# analog.net
KiCad netlist of a schematic drawn in Altium Designer
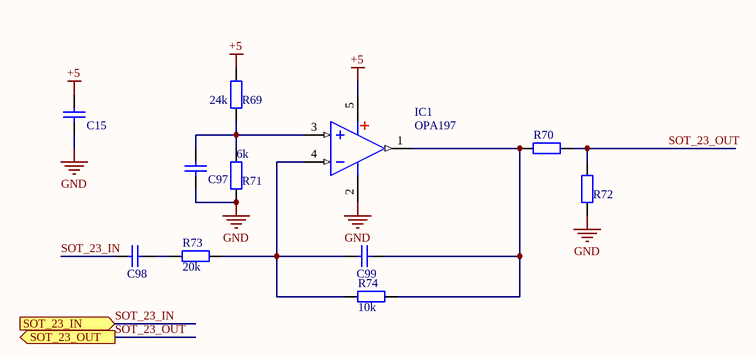
[diagram p0: analog.SchDoc]

(export (version "E")
  (design (tool "Eeschema 10.0.6"))
  (components
    (comp (ref "C15")
      (value "10nF (103) 10% 50V")
      (footprint "0603_C")
      (description "贴片电容")
      (libsource (lib "JLC") (part "0603 10nF (103) 10% 50V"))
    )
    (comp (ref "C97")
      (value "100nF (104) 10% 50V")
      (footprint "0603_C")
      (description "贴片电容")
      (libsource (lib "JLC") (part "0603 100nF (104) 10% 50V"))
    )
    (comp (ref "C98")
      (value "100nF (104) 10% 50V")
      (footprint "0603_C")
      (description "贴片电容")
      (libsource (lib "JLC") (part "0603 100nF (104) 10% 50V"))
    )
    (comp (ref "C99")
      (value "100nF (104) 10% 50V")
      (footprint "0603_C")
      (description "贴片电容")
      (libsource (lib "JLC") (part "0603 100nF (104) 10% 50V"))
    )
    (comp (ref "IC1")
      (value "OPA197")
      (footprint "SOT23-5N")
      (description "SOT23-5_轨至轨运放")
      (fields (field (name "版权归属") "源创客"))
      (libsource (lib "1.5   - 运放-功放") (part "SGM8521-5Pin"))
    )
    (comp (ref "R69")
      (value "24k")
      (footprint "0603_R")
      (description "贴片电阻")
      (libsource (lib "") (part "0603 110Ω (1100) 1%_1"))
    )
    (comp (ref "R70")
      (value "110Ω (1100) ±1%")
      (footprint "0603_R")
      (description "贴片电阻")
      (libsource (lib "JLC") (part "0603 110Ω (1100) 1%"))
    )
    (comp (ref "R71")
      (value "6k")
      (footprint "0603_R")
      (description "贴片电阻")
      (libsource (lib "") (part "0603 110Ω (1100) 1%_1"))
    )
    (comp (ref "R72")
      (value "110Ω (1100) ±1%")
      (footprint "0603_R")
      (description "贴片电阻")
      (libsource (lib "") (part "0603 110Ω (1100) 1%_1"))
    )
    (comp (ref "R73")
      (value "20k")
      (footprint "0603_R")
      (description "贴片电阻")
      (libsource (lib "JLC") (part "0603 110Ω (1100) 1%"))
    )
    (comp (ref "R74")
      (value "10k")
      (footprint "0603_R")
      (description "贴片电阻")
      (libsource (lib "JLC") (part "0603 110Ω (1100) 1%"))
    )
  )
  (nets
    (net (code "1") (name "+5") (class "Default")
      (node (ref "C15") (pin "2") (pinfunction "2_2") (pintype "passive"))
      (node (ref "IC1") (pin "5") (pinfunction "V+_5") (pintype "power_in"))
      (node (ref "R69") (pin "2") (pinfunction "2_2") (pintype "passive"))
    )
    (net (code "2") (name "/SOT_23_IN") (class "Default")
      (node (ref "C98") (pin "1") (pinfunction "1_1") (pintype "passive"))
    )
    (net (code "3") (name "/SOT_23_OUT") (class "Default")
      (node (ref "R70") (pin "2") (pinfunction "2_2") (pintype "passive"))
      (node (ref "R72") (pin "2") (pinfunction "2_2") (pintype "passive"))
    )
    (net (code "4") (name "GND") (class "Default")
      (node (ref "C15") (pin "1") (pinfunction "1_1") (pintype "passive"))
      (node (ref "C97") (pin "2") (pinfunction "2_2") (pintype "passive"))
      (node (ref "IC1") (pin "2") (pinfunction "V-_2") (pintype "power_in"))
      (node (ref "R71") (pin "1") (pinfunction "1_1") (pintype "passive"))
      (node (ref "R72") (pin "1") (pinfunction "1_1") (pintype "passive"))
    )
    (net (code "5") (name "Net-(C98-Pad2)") (class "Default")
      (node (ref "C98") (pin "2") (pinfunction "2_2") (pintype "passive"))
      (node (ref "R73") (pin "1") (pinfunction "1_1") (pintype "passive"))
    )
    (net (code "6") (name "Net-(IC1-IN+)") (class "Default")
      (node (ref "C97") (pin "1") (pinfunction "1_1") (pintype "passive"))
      (node (ref "IC1") (pin "3") (pinfunction "IN+_3") (pintype "input"))
      (node (ref "R69") (pin "1") (pinfunction "1_1") (pintype "passive"))
      (node (ref "R71") (pin "2") (pinfunction "2_2") (pintype "passive"))
    )
    (net (code "7") (name "Net-(IC1-IN-)") (class "Default")
      (node (ref "C99") (pin "2") (pinfunction "2_2") (pintype "passive"))
      (node (ref "IC1") (pin "4") (pinfunction "IN-_4") (pintype "input"))
      (node (ref "R73") (pin "2") (pinfunction "2_2") (pintype "passive"))
      (node (ref "R74") (pin "1") (pinfunction "1_1") (pintype "passive"))
    )
    (net (code "8") (name "Net-(IC1-OUT)") (class "Default")
      (node (ref "C99") (pin "1") (pinfunction "1_1") (pintype "passive"))
      (node (ref "IC1") (pin "1") (pinfunction "OUT_1") (pintype "output"))
      (node (ref "R70") (pin "1") (pinfunction "1_1") (pintype "passive"))
      (node (ref "R74") (pin "2") (pinfunction "2_2") (pintype "passive"))
    )
  )
)
